# CH32F203CBT6-R1.net
KiCad netlist of a schematic drawn in Altium Designer
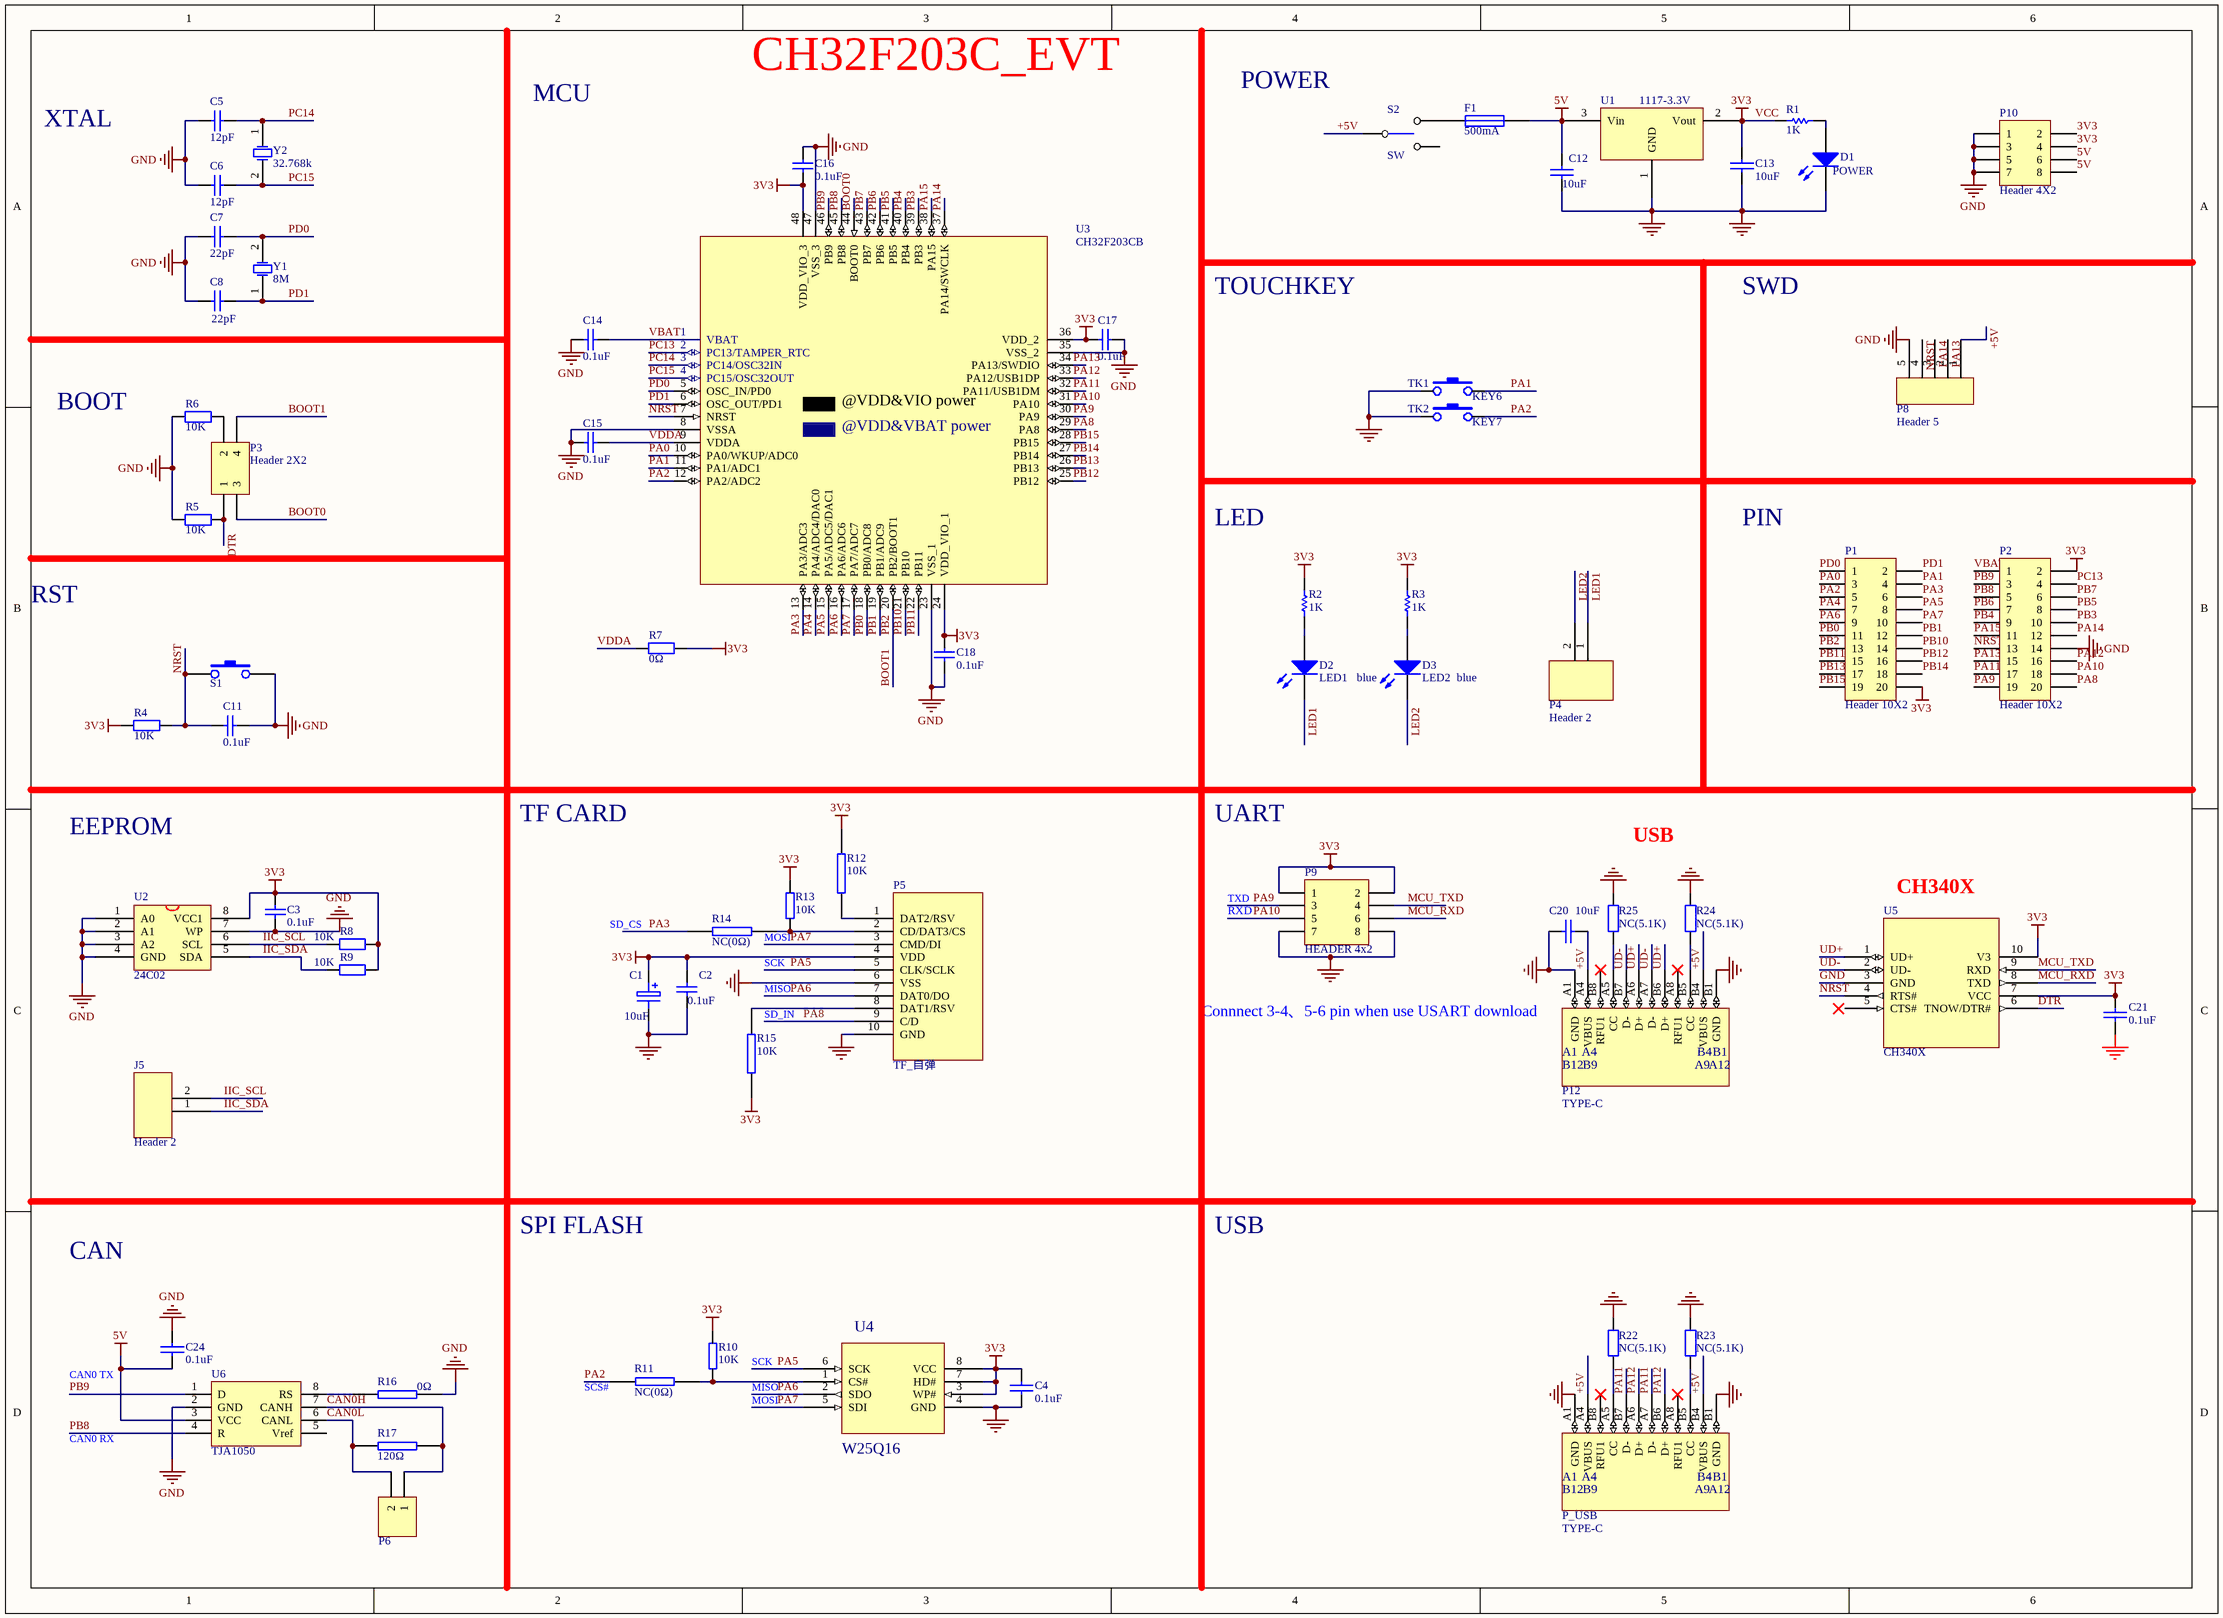
[diagram p0: CH32F203CBT6-R1.SchDoc]

(export (version "E")
  (design (tool "Eeschema 10.0.6"))
  (components
    (comp (ref "C1")
      (value "10uF")
      (footprint "3216")
      (description "Electrolytic Capacitor")
      (libsource (lib "*") (part "ELECTRO1"))
    )
    (comp (ref "C2")
      (value "0.1uF")
      (footprint "0603")
      (description "Capacitor")
      (fields (field (name "PUBLISHER") "Altium Limited"))
      (libsource (lib "*") (part "Cap"))
    )
    (comp (ref "C3")
      (value "0.1uF")
      (footprint "0603")
      (description "Capacitor")
      (fields (field (name "PUBLISHER") "Altium Limited"))
      (libsource (lib "Miscellaneous Devices") (part "Cap"))
    )
    (comp (ref "C4")
      (value "0.1uF")
      (footprint "0603")
      (description "Capacitor")
      (libsource (lib "*") (part "CAP"))
    )
    (comp (ref "C5")
      (value "12pF")
      (footprint "0603")
      (description "Capacitor")
      (fields (field (name "PUBLISHER") "Altium Limited"))
      (libsource (lib "Miscellaneous Devices") (part "Cap"))
    )
    (comp (ref "C6")
      (value "12pF")
      (footprint "0603")
      (description "Capacitor")
      (fields (field (name "PUBLISHER") "Altium Limited"))
      (libsource (lib "Miscellaneous Devices") (part "Cap"))
    )
    (comp (ref "C7")
      (value "22pF")
      (footprint "0603")
      (description "Capacitor")
      (fields (field (name "PUBLISHER") "Altium Limited"))
      (libsource (lib "Miscellaneous Devices") (part "Cap"))
    )
    (comp (ref "C8")
      (value "22pF")
      (footprint "0603")
      (description "Capacitor")
      (fields (field (name "PUBLISHER") "Altium Limited"))
      (libsource (lib "Miscellaneous Devices") (part "Cap"))
    )
    (comp (ref "C11")
      (value "0.1uF")
      (footprint "0603")
      (description "Capacitor")
      (fields (field (name "PUBLISHER") "Altium Limited"))
      (libsource (lib "Miscellaneous Devices") (part "Cap"))
    )
    (comp (ref "C12")
      (value "10uF")
      (footprint "3216")
      (description "Capacitor")
      (libsource (lib "") (part "CAP_1"))
    )
    (comp (ref "C13")
      (value "10uF")
      (footprint "0603")
      (description "Capacitor")
      (libsource (lib "") (part "CAP_1"))
    )
    (comp (ref "C14")
      (value "0.1uF")
      (footprint "0603")
      (description "Capacitor")
      (fields (field (name "PUBLISHER") "Altium Limited"))
      (libsource (lib "Miscellaneous Devices") (part "Cap"))
    )
    (comp (ref "C15")
      (value "0.1uF")
      (footprint "0603")
      (description "Capacitor")
      (fields (field (name "PUBLISHER") "Altium Limited"))
      (libsource (lib "Miscellaneous Devices") (part "Cap"))
    )
    (comp (ref "C16")
      (value "0.1uF")
      (footprint "0603")
      (description "Capacitor")
      (fields (field (name "PUBLISHER") "Altium Limited"))
      (libsource (lib "Miscellaneous Devices") (part "Cap"))
    )
    (comp (ref "C17")
      (value "0.1uF")
      (footprint "0603")
      (description "Capacitor")
      (fields (field (name "PUBLISHER") "Altium Limited"))
      (libsource (lib "Miscellaneous Devices") (part "Cap"))
    )
    (comp (ref "C18")
      (value "0.1uF")
      (footprint "0603")
      (description "Capacitor")
      (fields (field (name "PUBLISHER") "Altium Limited"))
      (libsource (lib "Miscellaneous Devices") (part "Cap"))
    )
    (comp (ref "C20")
      (value "10uF")
      (footprint "3216_C")
      (description "Capacitor")
      (libsource (lib "") (part "CAP_1"))
    )
    (comp (ref "C21")
      (value "0.1uF")
      (footprint "0603_C")
      (description "Capacitor")
      (libsource (lib "") (part "CAP_1"))
    )
    (comp (ref "C24")
      (value "0.1uF")
      (footprint "0603")
      (description "Capacitor")
      (libsource (lib "*") (part "CAP"))
    )
    (comp (ref "D1")
      (value "POWER")
      (footprint "0603L")
      (description "Typical INFRARED GaAs LED")
      (fields (field (name "PUBLISHER") "Altium Limited"))
      (libsource (lib "Miscellaneous Devices") (part "LED0"))
    )
    (comp (ref "D2")
      (value "LED1   blue")
      (footprint "0603L")
      (description "Typical INFRARED GaAs LED")
      (fields (field (name "PUBLISHER") "Altium Limited"))
      (libsource (lib "Miscellaneous Devices") (part "LED0"))
    )
    (comp (ref "D3")
      (value "LED2  blue")
      (footprint "0603L")
      (description "Typical INFRARED GaAs LED")
      (fields (field (name "PUBLISHER") "Altium Limited"))
      (libsource (lib "Miscellaneous Devices") (part "LED0"))
    )
    (comp (ref "F1")
      (value "500mA")
      (footprint "0603")
      (description "Fuse")
      (libsource (lib "*") (part "FUSE1"))
    )
    (comp (ref "J5") (value "Header 2") (footprint "SIP2 - 40mil") (libsource (lib "") (part "2HEAD_1")))
    (comp (ref "P1")
      (value "Header 10X2")
      (footprint "IDC20")
      (description "Header, 10-Pin, Dual row")
      (fields (field (name "PUBLISHER") "Altium Limited"))
      (libsource (lib "Miscellaneous Connectors") (part "Header 10X2"))
    )
    (comp (ref "P2")
      (value "Header 10X2")
      (footprint "IDC20")
      (description "Header, 10-Pin, Dual row")
      (fields (field (name "PUBLISHER") "Altium Limited"))
      (libsource (lib "Miscellaneous Connectors") (part "Header 10X2"))
    )
    (comp (ref "P3")
      (value "Header 2X2")
      (footprint "HDR2X2")
      (description "Header, 2-Pin, Dual row")
      (fields (field (name "PUBLISHER") "Altium Limited"))
      (libsource (lib "Miscellaneous Connectors") (part "Header 2X2"))
    )
    (comp (ref "P4") (value "Header 2") (footprint "SIP2 - 40mil") (libsource (lib "MYSCH") (part "2HEAD")))
    (comp (ref "P5") (value "TF_自弹") (footprint "TF_CARD") (libsource (lib "*") (part "TF_自弹")))
    (comp (ref "P6")
      (value "Header 2")
      (footprint "PORT2 4.5MM")
      (description "Header, 2-Pin")
      (fields (field (name "PUBLISHER") "Altium Limited"))
      (libsource (lib "Miscellaneous Connectors") (part "Header 2"))
    )
    (comp (ref "P8")
      (value "Header 5")
      (footprint "SIP5 - 40mil")
      (libsource (lib "PCB_Project1") (part "2HEAD"))
    )
    (comp (ref "P9")
      (value "HEADER 4x2")
      (footprint "MYPCB:IDC8-2.54mm")
      (description "Header, 4-Pin, Dual row")
      (libsource (lib "wch_sch_others") (part "HEADER 4x2"))
    )
    (comp (ref "P10")
      (value "Header 4X2")
      (footprint "IDC8")
      (description "Header, 4-Pin, Dual row")
      (fields (field (name "PUBLISHER") "Altium Limited"))
      (libsource (lib "Miscellaneous Connectors") (part "Header 4X2"))
    )
    (comp (ref "P12")
      (value "TYPE-C")
      (footprint "TYPE-C-Receptacle-2.0")
      (libsource (lib "*") (part "TYPE-C1"))
    )
    (comp (ref "P_USB")
      (value "TYPE-C")
      (footprint "TYPE-C-Receptacle-2.0")
      (libsource (lib "*") (part "TYPE-C1"))
    )
    (comp (ref "R1")
      (value "1K")
      (footprint "0603")
      (description "Semiconductor Resistor")
      (fields (field (name "PUBLISHER") "Altium Limited"))
      (libsource (lib "Miscellaneous Devices") (part "Res Semi"))
    )
    (comp (ref "R2")
      (value "1K")
      (footprint "0603")
      (description "Semiconductor Resistor")
      (fields (field (name "PUBLISHER") "Altium Limited"))
      (libsource (lib "Miscellaneous Devices") (part "Res Semi"))
    )
    (comp (ref "R3")
      (value "1K")
      (footprint "0603")
      (description "Semiconductor Resistor")
      (fields (field (name "PUBLISHER") "Altium Limited"))
      (libsource (lib "Miscellaneous Devices") (part "Res Semi"))
    )
    (comp (ref "R4")
      (value "10K")
      (footprint "0603")
      (description "Resistor")
      (fields (field (name "PUBLISHER") "Altium Limited"))
      (libsource (lib "Miscellaneous Devices") (part "Res2"))
    )
    (comp (ref "R5")
      (value "10K")
      (footprint "0603")
      (description "Resistor")
      (fields (field (name "PUBLISHER") "Altium Limited"))
      (libsource (lib "Miscellaneous Devices") (part "Res2"))
    )
    (comp (ref "R6")
      (value "10K")
      (footprint "0603")
      (description "Resistor")
      (fields (field (name "PUBLISHER") "Altium Limited"))
      (libsource (lib "Miscellaneous Devices") (part "Res2"))
    )
    (comp (ref "R7")
      (value "0Ω")
      (footprint "0603")
      (description "Resistor")
      (fields (field (name "PUBLISHER") "Altium Limited"))
      (libsource (lib "Miscellaneous Devices") (part "Res2"))
    )
    (comp (ref "R8")
      (value "10K")
      (footprint "0603")
      (description "Resistor")
      (fields (field (name "PUBLISHER") "Altium Limited"))
      (libsource (lib "Miscellaneous Devices") (part "Res2"))
    )
    (comp (ref "R9")
      (value "10K")
      (footprint "0603")
      (description "Resistor")
      (fields (field (name "PUBLISHER") "Altium Limited"))
      (libsource (lib "Miscellaneous Devices") (part "Res2"))
    )
    (comp (ref "R10") (value "10K") (footprint "0603") (libsource (lib "*") (part "DZ")))
    (comp (ref "R11") (value "NC(0Ω)") (footprint "0603") (libsource (lib "*") (part "RES2")))
    (comp (ref "R12") (value "10K") (footprint "0603") (libsource (lib "*") (part "RES2")))
    (comp (ref "R13") (value "10K") (footprint "0603") (libsource (lib "*") (part "DZ")))
    (comp (ref "R14") (value "NC(0Ω)") (footprint "0603") (libsource (lib "*") (part "RES2")))
    (comp (ref "R15") (value "10K") (footprint "0603") (libsource (lib "*") (part "RES2")))
    (comp (ref "R16") (value "0Ω") (footprint "0603") (libsource (lib "*") (part "RES2")))
    (comp (ref "R17") (value "120Ω") (footprint "0603") (libsource (lib "*") (part "RES2")))
    (comp (ref "R22")
      (value "NC(5.1K)")
      (footprint "0603")
      (description "Resistor")
      (libsource (lib "") (part "Res2_1"))
    )
    (comp (ref "R23")
      (value "NC(5.1K)")
      (footprint "0603")
      (description "Resistor")
      (libsource (lib "") (part "Res2_1"))
    )
    (comp (ref "R24")
      (value "NC(5.1K)")
      (footprint "0603")
      (description "Resistor")
      (libsource (lib "") (part "Res2_1"))
    )
    (comp (ref "R25")
      (value "NC(5.1K)")
      (footprint "0603")
      (description "Resistor")
      (libsource (lib "") (part "Res2_1"))
    )
    (comp (ref "S1") (value "KEY") (footprint "贴片按键") (libsource (lib "CCDXPLIB") (part "KEY")))
    (comp (ref "S2") (value "SW") (footprint "KEY2") (libsource (lib "MYSCH") (part "SW")))
    (comp (ref "TK1") (value "KEY6") (footprint "KEY68") (libsource (lib "*") (part "KEY")))
    (comp (ref "TK2") (value "KEY7") (footprint "KEY68") (libsource (lib "*") (part "KEY")))
    (comp (ref "U1")
      (value "1117-3.3V")
      (footprint "SOT-223")
      (libsource (lib "wch_sch_others") (part "1117-3.3V"))
    )
    (comp (ref "U2") (value "24C02") (footprint "SOP8") (libsource (lib "Elite_SCH") (part "24C256")))
    (comp (ref "U3")
      (value "CH32F203CB")
      (footprint "LQFP48")
      (description "ARM M3 HD-MCU, 144MHz, 8*UART, 10*Timer, 4*OPA")
      (libsource (lib "CHXXX") (part "CH32F203CB"))
    )
    (comp (ref "U4")
      (value "W25Q16")
      (footprint "016 SO-8")
      (libsource (lib "*") (part "Pro89C.tmp_25F512_2"))
    )
    (comp (ref "U5")
      (value "CH340X")
      (footprint "MSOP10")
      (description "USB to TTL Serial / UART")
      (libsource (lib "CHXXX") (part "CH340X"))
    )
    (comp (ref "U6") (value "TJA1050") (footprint "SOP8") (libsource (lib "CAN") (part "Component_1")))
    (comp (ref "Y1")
      (value "8M")
      (footprint "XT62/28")
      (description "Crystal Oscillator")
      (fields (field (name "PUBLISHER") "Altium Limited"))
      (libsource (lib "Miscellaneous Devices") (part "XTAL"))
    )
    (comp (ref "Y2")
      (value "32.768k")
      (footprint "FC-135")
      (description "Crystal Oscillator")
      (fields (field (name "PUBLISHER") "Altium Limited"))
      (libsource (lib "Miscellaneous Devices") (part "XTAL"))
    )
  )
  (nets
    (net (code "1") (name "/+5V") (class "Default")
      (node (ref "C20") (pin "2") (pinfunction "2_2") (pintype "passive"))
      (node (ref "P12") (pin "A4") (pinfunction "VBUS_A4") (pintype "bidirectional"))
      (node (ref "P12") (pin "B4") (pinfunction "VBUS_B4") (pintype "bidirectional"))
      (node (ref "P8") (pin "1") (pintype "passive"))
      (node (ref "P_USB") (pin "A4") (pinfunction "VBUS_A4") (pintype "bidirectional"))
      (node (ref "P_USB") (pin "B4") (pinfunction "VBUS_B4") (pintype "bidirectional"))
      (node (ref "S2") (pin "1") (pinfunction "1_1") (pintype "passive"))
    )
    (net (code "3") (name "/BOOT0") (class "Default")
      (node (ref "P3") (pin "3") (pinfunction "3_3") (pintype "passive"))
      (node (ref "U3") (pin "44") (pinfunction "BOOT0_44") (pintype "input"))
    )
    (net (code "4") (name "/BOOT1") (class "Default")
      (node (ref "P1") (pin "13") (pinfunction "13_13") (pintype "passive"))
      (node (ref "P3") (pin "4") (pinfunction "4_4") (pintype "passive"))
      (node (ref "U3") (pin "20") (pinfunction "PB2/BOOT1_20") (pintype "bidirectional"))
    )
    (net (code "5") (name "/CAN0H") (class "Default")
      (node (ref "P6") (pin "1") (pinfunction "1_1") (pintype "passive"))
      (node (ref "R17") (pin "1") (pinfunction "1_1") (pintype "passive"))
      (node (ref "U6") (pin "7") (pinfunction "CANH_7") (pintype "passive"))
    )
    (net (code "6") (name "/CAN0L") (class "Default")
      (node (ref "P6") (pin "2") (pinfunction "2_2") (pintype "passive"))
      (node (ref "R17") (pin "2") (pinfunction "2_2") (pintype "passive"))
      (node (ref "U6") (pin "6") (pinfunction "CANL_6") (pintype "passive"))
    )
    (net (code "7") (name "/DTR") (class "Default")
      (node (ref "P3") (pin "1") (pinfunction "1_1") (pintype "passive"))
      (node (ref "R5") (pin "1") (pinfunction "1_1") (pintype "passive"))
      (node (ref "U5") (pin "6") (pinfunction "TNOW/DTR#_6") (pintype "output"))
    )
    (net (code "8") (name "/IIC_SCL") (class "Default")
      (node (ref "J5") (pin "2") (pintype "passive"))
      (node (ref "R8") (pin "2") (pinfunction "2_2") (pintype "passive"))
      (node (ref "U2") (pin "6") (pinfunction "SCL_6") (pintype "passive"))
    )
    (net (code "9") (name "/IIC_SDA") (class "Default")
      (node (ref "J5") (pin "1") (pintype "passive"))
      (node (ref "R9") (pin "2") (pinfunction "2_2") (pintype "passive"))
      (node (ref "U2") (pin "5") (pinfunction "SDA_5") (pintype "passive"))
    )
    (net (code "10") (name "/LED1") (class "Default")
      (node (ref "D2") (pin "2") (pinfunction "K_2") (pintype "passive"))
      (node (ref "P4") (pin "1") (pintype "passive"))
    )
    (net (code "11") (name "/LED2") (class "Default")
      (node (ref "D3") (pin "2") (pinfunction "K_2") (pintype "passive"))
      (node (ref "P4") (pin "2") (pintype "passive"))
    )
    (net (code "12") (name "/MCU_RXD") (class "Default")
      (node (ref "P9") (pin "6") (pinfunction "6_6") (pintype "passive"))
      (node (ref "U5") (pin "8") (pinfunction "TXD_8") (pintype "output"))
    )
    (net (code "13") (name "/MCU_TXD") (class "Default")
      (node (ref "P9") (pin "4") (pinfunction "4_4") (pintype "passive"))
      (node (ref "U5") (pin "9") (pinfunction "RXD_9") (pintype "input"))
    )
    (net (code "14") (name "/NRST") (class "Default")
      (node (ref "C11") (pin "2") (pinfunction "2_2") (pintype "passive"))
      (node (ref "P2") (pin "13") (pinfunction "13_13") (pintype "passive"))
      (node (ref "P8") (pin "4") (pintype "passive"))
      (node (ref "R4") (pin "1") (pinfunction "1_1") (pintype "passive"))
      (node (ref "S1") (pin "1") (pinfunction "1_1") (pintype "passive"))
      (node (ref "U3") (pin "7") (pinfunction "NRST_7") (pintype "input"))
      (node (ref "U5") (pin "4") (pinfunction "RTS#_4") (pintype "output"))
    )
    (net (code "15") (name "/PA0") (class "Default")
      (node (ref "P1") (pin "3") (pinfunction "3_3") (pintype "passive"))
      (node (ref "U3") (pin "10") (pinfunction "PA0/WKUP/ADC0_10") (pintype "bidirectional"))
    )
    (net (code "16") (name "/PA1") (class "Default")
      (node (ref "P1") (pin "4") (pinfunction "4_4") (pintype "passive"))
      (node (ref "TK1") (pin "1") (pintype "passive"))
      (node (ref "U3") (pin "11") (pinfunction "PA1/ADC1_11") (pintype "bidirectional"))
    )
    (net (code "17") (name "/PA2") (class "Default")
      (node (ref "P1") (pin "5") (pinfunction "5_5") (pintype "passive"))
      (node (ref "R11") (pin "2") (pinfunction "2_2") (pintype "passive"))
      (node (ref "TK2") (pin "1") (pintype "passive"))
      (node (ref "U3") (pin "12") (pinfunction "PA2/ADC2_12") (pintype "bidirectional"))
    )
    (net (code "18") (name "/PA3") (class "Default")
      (node (ref "P1") (pin "6") (pinfunction "6_6") (pintype "passive"))
      (node (ref "R14") (pin "2") (pinfunction "2_2") (pintype "passive"))
      (node (ref "U3") (pin "13") (pinfunction "PA3/ADC3_13") (pintype "bidirectional"))
    )
    (net (code "19") (name "/PA4") (class "Default")
      (node (ref "P1") (pin "7") (pinfunction "7_7") (pintype "passive"))
      (node (ref "U3") (pin "14") (pinfunction "PA4/ADC4/DAC0_14") (pintype "bidirectional"))
    )
    (net (code "20") (name "/PA5") (class "Default")
      (node (ref "P1") (pin "8") (pinfunction "8_8") (pintype "passive"))
      (node (ref "P5") (pin "5") (pinfunction "CLK/SCLK_5") (pintype "passive"))
      (node (ref "U3") (pin "15") (pinfunction "PA5/ADC5/DAC1_15") (pintype "bidirectional"))
      (node (ref "U4") (pin "6") (pinfunction "SCK_6") (pintype "input"))
    )
    (net (code "21") (name "/PA6") (class "Default")
      (node (ref "P1") (pin "9") (pinfunction "9_9") (pintype "passive"))
      (node (ref "P5") (pin "7") (pinfunction "DAT0/DO_7") (pintype "passive"))
      (node (ref "U3") (pin "16") (pinfunction "PA6/ADC6_16") (pintype "bidirectional"))
      (node (ref "U4") (pin "2") (pinfunction "SDO_2") (pintype "output"))
    )
    (net (code "22") (name "/PA7") (class "Default")
      (node (ref "P1") (pin "10") (pinfunction "10_10") (pintype "passive"))
      (node (ref "P5") (pin "3") (pinfunction "CMD/DI_3") (pintype "passive"))
      (node (ref "U3") (pin "17") (pinfunction "PA7/ADC7_17") (pintype "bidirectional"))
      (node (ref "U4") (pin "5") (pinfunction "SDI_5") (pintype "input"))
    )
    (net (code "23") (name "/PA8") (class "Default")
      (node (ref "P2") (pin "20") (pinfunction "20_20") (pintype "passive"))
      (node (ref "P5") (pin "9") (pinfunction "C/D_9") (pintype "passive"))
      (node (ref "U3") (pin "29") (pinfunction "PA8_29") (pintype "bidirectional"))
    )
    (net (code "24") (name "/PA9") (class "Default")
      (node (ref "P2") (pin "19") (pinfunction "19_19") (pintype "passive"))
      (node (ref "P9") (pin "3") (pinfunction "3_3") (pintype "passive"))
      (node (ref "U3") (pin "30") (pinfunction "PA9_30") (pintype "bidirectional"))
    )
    (net (code "25") (name "/PA10") (class "Default")
      (node (ref "P2") (pin "18") (pinfunction "18_18") (pintype "passive"))
      (node (ref "P9") (pin "5") (pinfunction "5_5") (pintype "passive"))
      (node (ref "U3") (pin "31") (pinfunction "PA10_31") (pintype "bidirectional"))
    )
    (net (code "26") (name "/PA11") (class "Default")
      (node (ref "P2") (pin "17") (pinfunction "17_17") (pintype "passive"))
      (node (ref "P_USB") (pin "A7") (pinfunction "D-_A7") (pintype "bidirectional"))
      (node (ref "P_USB") (pin "B7") (pinfunction "D-_B7") (pintype "bidirectional"))
      (node (ref "U3") (pin "32") (pinfunction "PA11/USB1DM_32") (pintype "bidirectional"))
    )
    (net (code "27") (name "/PA12") (class "Default")
      (node (ref "P2") (pin "16") (pinfunction "16_16") (pintype "passive"))
      (node (ref "P_USB") (pin "A6") (pinfunction "D+_A6") (pintype "bidirectional"))
      (node (ref "P_USB") (pin "B6") (pinfunction "D+_B6") (pintype "bidirectional"))
      (node (ref "U3") (pin "33") (pinfunction "PA12/USB1DP_33") (pintype "bidirectional"))
    )
    (net (code "28") (name "/PA13") (class "Default")
      (node (ref "P2") (pin "15") (pinfunction "15_15") (pintype "passive"))
      (node (ref "P8") (pin "2") (pintype "passive"))
      (node (ref "U3") (pin "34") (pinfunction "PA13/SWDIO_34") (pintype "bidirectional"))
    )
    (net (code "29") (name "/PA14") (class "Default")
      (node (ref "P2") (pin "12") (pinfunction "12_12") (pintype "passive"))
      (node (ref "P8") (pin "3") (pintype "passive"))
      (node (ref "U3") (pin "37") (pinfunction "PA14/SWCLK_37") (pintype "bidirectional"))
    )
    (net (code "30") (name "/PA15") (class "Default")
      (node (ref "P2") (pin "11") (pinfunction "11_11") (pintype "passive"))
      (node (ref "U3") (pin "38") (pinfunction "PA15_38") (pintype "bidirectional"))
    )
    (net (code "31") (name "/PB0") (class "Default")
      (node (ref "P1") (pin "11") (pinfunction "11_11") (pintype "passive"))
      (node (ref "U3") (pin "18") (pinfunction "PB0/ADC8_18") (pintype "bidirectional"))
    )
    (net (code "32") (name "/PB1") (class "Default")
      (node (ref "P1") (pin "12") (pinfunction "12_12") (pintype "passive"))
      (node (ref "U3") (pin "19") (pinfunction "PB1/ADC9_19") (pintype "bidirectional"))
    )
    (net (code "33") (name "/PB3") (class "Default")
      (node (ref "P2") (pin "10") (pinfunction "10_10") (pintype "passive"))
      (node (ref "U3") (pin "39") (pinfunction "PB3_39") (pintype "bidirectional"))
    )
    (net (code "34") (name "/PB4") (class "Default")
      (node (ref "P2") (pin "9") (pinfunction "9_9") (pintype "passive"))
      (node (ref "U3") (pin "40") (pinfunction "PB4_40") (pintype "bidirectional"))
    )
    (net (code "35") (name "/PB5") (class "Default")
      (node (ref "P2") (pin "8") (pinfunction "8_8") (pintype "passive"))
      (node (ref "U3") (pin "41") (pinfunction "PB5_41") (pintype "bidirectional"))
    )
    (net (code "36") (name "/PB6") (class "Default")
      (node (ref "P2") (pin "7") (pinfunction "7_7") (pintype "passive"))
      (node (ref "U3") (pin "42") (pinfunction "PB6_42") (pintype "bidirectional"))
    )
    (net (code "37") (name "/PB7") (class "Default")
      (node (ref "P2") (pin "6") (pinfunction "6_6") (pintype "passive"))
      (node (ref "U3") (pin "43") (pinfunction "PB7_43") (pintype "bidirectional"))
    )
    (net (code "38") (name "/PB8") (class "Default")
      (node (ref "P2") (pin "5") (pinfunction "5_5") (pintype "passive"))
      (node (ref "U3") (pin "45") (pinfunction "PB8_45") (pintype "bidirectional"))
      (node (ref "U6") (pin "4") (pinfunction "R_4") (pintype "passive"))
    )
    (net (code "39") (name "/PB9") (class "Default")
      (node (ref "P2") (pin "3") (pinfunction "3_3") (pintype "passive"))
      (node (ref "U3") (pin "46") (pinfunction "PB9_46") (pintype "bidirectional"))
      (node (ref "U6") (pin "1") (pinfunction "D_1") (pintype "passive"))
    )
    (net (code "40") (name "/PB10") (class "Default")
      (node (ref "P1") (pin "14") (pinfunction "14_14") (pintype "passive"))
      (node (ref "U3") (pin "21") (pinfunction "PB10_21") (pintype "bidirectional"))
    )
    (net (code "41") (name "/PB11") (class "Default")
      (node (ref "P1") (pin "15") (pinfunction "15_15") (pintype "passive"))
      (node (ref "U3") (pin "22") (pinfunction "PB11_22") (pintype "bidirectional"))
    )
    (net (code "42") (name "/PB12") (class "Default")
      (node (ref "P1") (pin "16") (pinfunction "16_16") (pintype "passive"))
      (node (ref "U3") (pin "25") (pinfunction "PB12_25") (pintype "bidirectional"))
    )
    (net (code "43") (name "/PB13") (class "Default")
      (node (ref "P1") (pin "17") (pinfunction "17_17") (pintype "passive"))
      (node (ref "U3") (pin "26") (pinfunction "PB13_26") (pintype "bidirectional"))
    )
    (net (code "44") (name "/PB14") (class "Default")
      (node (ref "P1") (pin "18") (pinfunction "18_18") (pintype "passive"))
      (node (ref "U3") (pin "27") (pinfunction "PB14_27") (pintype "bidirectional"))
    )
    (net (code "45") (name "/PB15") (class "Default")
      (node (ref "P1") (pin "19") (pinfunction "19_19") (pintype "passive"))
      (node (ref "U3") (pin "28") (pinfunction "PB15_28") (pintype "bidirectional"))
    )
    (net (code "46") (name "/PC13") (class "Default")
      (node (ref "P2") (pin "4") (pinfunction "4_4") (pintype "passive"))
      (node (ref "U3") (pin "2") (pinfunction "PC13/TAMPER_RTC_2") (pintype "bidirectional"))
    )
    (net (code "47") (name "/PC14") (class "Default")
      (node (ref "C5") (pin "1") (pinfunction "1_1") (pintype "passive"))
      (node (ref "U3") (pin "3") (pinfunction "PC14/OSC32IN_3") (pintype "bidirectional"))
      (node (ref "Y2") (pin "1") (pinfunction "OSC1_1") (pintype "passive"))
    )
    (net (code "48") (name "/PC15") (class "Default")
      (node (ref "C6") (pin "1") (pinfunction "1_1") (pintype "passive"))
      (node (ref "U3") (pin "4") (pinfunction "PC15/OSC32OUT_4") (pintype "bidirectional"))
      (node (ref "Y2") (pin "2") (pinfunction "OSC2_2") (pintype "passive"))
    )
    (net (code "49") (name "/PD0") (class "Default")
      (node (ref "C7") (pin "2") (pinfunction "2_2") (pintype "passive"))
      (node (ref "P1") (pin "1") (pinfunction "1_1") (pintype "passive"))
      (node (ref "U3") (pin "5") (pinfunction "OSC_IN/PD0_5") (pintype "bidirectional"))
      (node (ref "Y1") (pin "2") (pinfunction "OSC2_2") (pintype "passive"))
    )
    (net (code "50") (name "/PD1") (class "Default")
      (node (ref "C8") (pin "2") (pinfunction "2_2") (pintype "passive"))
      (node (ref "P1") (pin "2") (pinfunction "2_2") (pintype "passive"))
      (node (ref "U3") (pin "6") (pinfunction "OSC_OUT/PD1_6") (pintype "bidirectional"))
      (node (ref "Y1") (pin "1") (pinfunction "OSC1_1") (pintype "passive"))
    )
    (net (code "51") (name "/UD+") (class "Default")
      (node (ref "P12") (pin "A6") (pinfunction "D+_A6") (pintype "bidirectional"))
      (node (ref "P12") (pin "B6") (pinfunction "D+_B6") (pintype "bidirectional"))
      (node (ref "U5") (pin "1") (pinfunction "UD+_1") (pintype "bidirectional"))
    )
    (net (code "52") (name "/UD-") (class "Default")
      (node (ref "P12") (pin "A7") (pinfunction "D-_A7") (pintype "bidirectional"))
      (node (ref "P12") (pin "B7") (pinfunction "D-_B7") (pintype "bidirectional"))
      (node (ref "U5") (pin "2") (pinfunction "UD-_2") (pintype "bidirectional"))
    )
    (net (code "53") (name "/VBAT") (class "Default")
      (node (ref "C14") (pin "1") (pinfunction "1_1") (pintype "passive"))
      (node (ref "P2") (pin "1") (pinfunction "1_1") (pintype "passive"))
      (node (ref "U3") (pin "1") (pinfunction "VBAT_1") (pintype "power_in"))
    )
    (net (code "54") (name "/VDDA") (class "Default")
      (node (ref "C15") (pin "1") (pinfunction "1_1") (pintype "passive"))
      (node (ref "R7") (pin "2") (pinfunction "2_2") (pintype "passive"))
      (node (ref "U3") (pin "9") (pinfunction "VDDA_9") (pintype "power_in"))
    )
    (net (code "55") (name "3V3") (class "Default")
      (node (ref "C1") (pin "1") (pinfunction "1_1") (pintype "passive"))
      (node (ref "C13") (pin "1") (pinfunction "1_1") (pintype "passive"))
      (node (ref "C16") (pin "2") (pinfunction "2_2") (pintype "passive"))
      (node (ref "C17") (pin "2") (pinfunction "2_2") (pintype "passive"))
      (node (ref "C18") (pin "2") (pinfunction "2_2") (pintype "passive"))
      (node (ref "C2") (pin "1") (pinfunction "1_1") (pintype "passive"))
      (node (ref "C21") (pin "1") (pinfunction "1_1") (pintype "passive"))
      (node (ref "C3") (pin "2") (pinfunction "2_2") (pintype "passive"))
      (node (ref "C4") (pin "2") (pinfunction "2_2") (pintype "passive"))
      (node (ref "P1") (pin "20") (pinfunction "20_20") (pintype "passive"))
      (node (ref "P10") (pin "2") (pinfunction "2_2") (pintype "passive"))
      (node (ref "P10") (pin "4") (pinfunction "4_4") (pintype "passive"))
      (node (ref "P2") (pin "2") (pinfunction "2_2") (pintype "passive"))
      (node (ref "P5") (pin "4") (pinfunction "VDD_4") (pintype "passive"))
      (node (ref "P9") (pin "1") (pinfunction "1_1") (pintype "passive"))
      (node (ref "P9") (pin "2") (pinfunction "2_2") (pintype "passive"))
      (node (ref "R1") (pin "2") (pinfunction "2_2") (pintype "passive"))
      (node (ref "R10") (pin "2") (pintype "passive"))
      (node (ref "R12") (pin "2") (pinfunction "2_2") (pintype "passive"))
      (node (ref "R13") (pin "2") (pintype "passive"))
      (node (ref "R15") (pin "1") (pinfunction "1_1") (pintype "passive"))
      (node (ref "R2") (pin "1") (pinfunction "1_1") (pintype "passive"))
      (node (ref "R3") (pin "1") (pinfunction "1_1") (pintype "passive"))
      (node (ref "R4") (pin "2") (pinfunction "2_2") (pintype "passive"))
      (node (ref "R7") (pin "1") (pinfunction "1_1") (pintype "passive"))
      (node (ref "R8") (pin "1") (pinfunction "1_1") (pintype "passive"))
      (node (ref "R9") (pin "1") (pinfunction "1_1") (pintype "passive"))
      (node (ref "U1") (pin "2") (pinfunction "Vout_2") (pintype "passive"))
      (node (ref "U2") (pin "8") (pinfunction "VCC1_8") (pintype "passive"))
      (node (ref "U3") (pin "24") (pinfunction "VDD_VIO_1_24") (pintype "power_in"))
      (node (ref "U3") (pin "36") (pinfunction "VDD_2_36") (pintype "power_in"))
      (node (ref "U3") (pin "48") (pinfunction "VDD_VIO_3_48") (pintype "power_in"))
      (node (ref "U4") (pin "3") (pinfunction "WP#_3") (pintype "input"))
      (node (ref "U4") (pin "7") (pinfunction "HD#_7") (pintype "power_in"))
      (node (ref "U4") (pin "8") (pinfunction "VCC_8") (pintype "power_in"))
      (node (ref "U5") (pin "10") (pinfunction "V3_10") (pintype "power_in"))
      (node (ref "U5") (pin "7") (pinfunction "VCC_7") (pintype "power_in"))
    )
    (net (code "56") (name "5V") (class "Default")
      (node (ref "C12") (pin "1") (pinfunction "1_1") (pintype "passive"))
      (node (ref "C24") (pin "2") (pinfunction "2_2") (pintype "passive"))
      (node (ref "F1") (pin "2") (pinfunction "2_2") (pintype "passive"))
      (node (ref "P10") (pin "6") (pinfunction "6_6") (pintype "passive"))
      (node (ref "P10") (pin "8") (pinfunction "8_8") (pintype "passive"))
      (node (ref "U1") (pin "3") (pinfunction "Vin_3") (pintype "passive"))
      (node (ref "U6") (pin "3") (pinfunction "VCC_3") (pintype "passive"))
    )
    (net (code "57") (name "GND") (class "Default")
      (node (ref "C1") (pin "2") (pinfunction "2_2") (pintype "passive"))
      (node (ref "C11") (pin "1") (pinfunction "1_1") (pintype "passive"))
      (node (ref "C12") (pin "2") (pinfunction "2_2") (pintype "passive"))
      (node (ref "C13") (pin "2") (pinfunction "2_2") (pintype "passive"))
      (node (ref "C14") (pin "2") (pinfunction "2_2") (pintype "passive"))
      (node (ref "C15") (pin "2") (pinfunction "2_2") (pintype "passive"))
      (node (ref "C16") (pin "1") (pinfunction "1_1") (pintype "passive"))
      (node (ref "C17") (pin "1") (pinfunction "1_1") (pintype "passive"))
      (node (ref "C18") (pin "1") (pinfunction "1_1") (pintype "passive"))
      (node (ref "C2") (pin "2") (pinfunction "2_2") (pintype "passive"))
      (node (ref "C20") (pin "1") (pinfunction "1_1") (pintype "passive"))
      (node (ref "C21") (pin "2") (pinfunction "2_2") (pintype "passive"))
      (node (ref "C24") (pin "1") (pinfunction "1_1") (pintype "passive"))
      (node (ref "C3") (pin "1") (pinfunction "1_1") (pintype "passive"))
      (node (ref "C4") (pin "1") (pinfunction "1_1") (pintype "passive"))
      (node (ref "C5") (pin "2") (pinfunction "2_2") (pintype "passive"))
      (node (ref "C6") (pin "2") (pinfunction "2_2") (pintype "passive"))
      (node (ref "C7") (pin "1") (pinfunction "1_1") (pintype "passive"))
      (node (ref "C8") (pin "1") (pinfunction "1_1") (pintype "passive"))
      (node (ref "D1") (pin "2") (pinfunction "K_2") (pintype "passive"))
      (node (ref "P10") (pin "1") (pinfunction "1_1") (pintype "passive"))
      (node (ref "P10") (pin "3") (pinfunction "3_3") (pintype "passive"))
      (node (ref "P10") (pin "5") (pinfunction "5_5") (pintype "passive"))
      (node (ref "P10") (pin "7") (pinfunction "7_7") (pintype "passive"))
      (node (ref "P12") (pin "A1") (pinfunction "GND_A1") (pintype "bidirectional"))
      (node (ref "P12") (pin "B1") (pinfunction "GND_B1") (pintype "bidirectional"))
      (node (ref "P2") (pin "14") (pinfunction "14_14") (pintype "passive"))
      (node (ref "P5") (pin "10") (pinfunction "GND_10") (pintype "passive"))
      (node (ref "P5") (pin "6") (pinfunction "VSS_6") (pintype "passive"))
      (node (ref "P8") (pin "5") (pintype "passive"))
      (node (ref "P9") (pin "7") (pinfunction "7_7") (pintype "passive"))
      (node (ref "P9") (pin "8") (pinfunction "8_8") (pintype "passive"))
      (node (ref "P_USB") (pin "A1") (pinfunction "GND_A1") (pintype "bidirectional"))
      (node (ref "P_USB") (pin "B1") (pinfunction "GND_B1") (pintype "bidirectional"))
      (node (ref "R16") (pin "1") (pinfunction "1_1") (pintype "passive"))
      (node (ref "R22") (pin "2") (pinfunction "2_2") (pintype "passive"))
      (node (ref "R23") (pin "2") (pinfunction "2_2") (pintype "passive"))
      (node (ref "R24") (pin "2") (pinfunction "2_2") (pintype "passive"))
      (node (ref "R25") (pin "2") (pinfunction "2_2") (pintype "passive"))
      (node (ref "R5") (pin "2") (pinfunction "2_2") (pintype "passive"))
      (node (ref "R6") (pin "2") (pinfunction "2_2") (pintype "passive"))
      (node (ref "S1") (pin "3") (pinfunction "3_3") (pintype "passive"))
      (node (ref "TK1") (pin "3") (pintype "passive"))
      (node (ref "TK2") (pin "3") (pintype "passive"))
      (node (ref "U1") (pin "1") (pinfunction "GND_1") (pintype "passive"))
      (node (ref "U2") (pin "1") (pinfunction "A0_1") (pintype "passive"))
      (node (ref "U2") (pin "2") (pinfunction "A1_2") (pintype "passive"))
      (node (ref "U2") (pin "3") (pinfunction "A2_3") (pintype "passive"))
      (node (ref "U2") (pin "4") (pinfunction "GND_4") (pintype "passive"))
      (node (ref "U2") (pin "7") (pinfunction "WP_7") (pintype "passive"))
      (node (ref "U3") (pin "23") (pinfunction "VSS_1_23") (pintype "power_in"))
      (node (ref "U3") (pin "35") (pinfunction "VSS_2_35") (pintype "power_in"))
      (node (ref "U3") (pin "47") (pinfunction "VSS_3_47") (pintype "power_in"))
      (node (ref "U3") (pin "8") (pinfunction "VSSA_8") (pintype "power_in"))
      (node (ref "U4") (pin "4") (pinfunction "GND_4") (pintype "power_in"))
      (node (ref "U5") (pin "3") (pinfunction "GND_3") (pintype "power_in"))
      (node (ref "U6") (pin "2") (pinfunction "GND_2") (pintype "passive"))
    )
    (net (code "58") (name "Net-(D1-A)") (class "Default")
      (node (ref "D1") (pin "1") (pinfunction "A_1") (pintype "passive"))
      (node (ref "R1") (pin "1") (pinfunction "1_1") (pintype "passive"))
    )
    (net (code "59") (name "Net-(D2-A)") (class "Default")
      (node (ref "D2") (pin "1") (pinfunction "A_1") (pintype "passive"))
      (node (ref "R2") (pin "2") (pinfunction "2_2") (pintype "passive"))
    )
    (net (code "60") (name "Net-(D3-A)") (class "Default")
      (node (ref "D3") (pin "1") (pinfunction "A_1") (pintype "passive"))
      (node (ref "R3") (pin "2") (pinfunction "2_2") (pintype "passive"))
    )
    (net (code "61") (name "Net-(F1-Pad1)") (class "Default")
      (node (ref "F1") (pin "1") (pinfunction "1_1") (pintype "passive"))
      (node (ref "S2") (pin "2") (pinfunction "2_2") (pintype "passive"))
    )
    (net (code "62") (name "Net-(P3-Pad2)") (class "Default")
      (node (ref "P3") (pin "2") (pinfunction "2_2") (pintype "passive"))
      (node (ref "R6") (pin "1") (pinfunction "1_1") (pintype "passive"))
    )
    (net (code "63") (name "Net-(P5-CD{slash}DAT3{slash}CS)") (class "Default")
      (node (ref "P5") (pin "2") (pinfunction "CD/DAT3/CS_2") (pintype "passive"))
      (node (ref "R13") (pin "1") (pintype "passive"))
      (node (ref "R14") (pin "1") (pinfunction "1_1") (pintype "passive"))
    )
    (net (code "64") (name "Net-(P5-DAT1{slash}RSV)") (class "Default")
      (node (ref "P5") (pin "8") (pinfunction "DAT1/RSV_8") (pintype "passive"))
      (node (ref "R15") (pin "2") (pinfunction "2_2") (pintype "passive"))
    )
    (net (code "65") (name "Net-(P5-DAT2{slash}RSV)") (class "Default")
      (node (ref "P5") (pin "1") (pinfunction "DAT2/RSV_1") (pintype "passive"))
      (node (ref "R12") (pin "1") (pinfunction "1_1") (pintype "passive"))
    )
    (net (code "66") (name "Net-(P12-CC-PadA5)") (class "Default")
      (node (ref "P12") (pin "A5") (pinfunction "CC_A5") (pintype "bidirectional"))
      (node (ref "R25") (pin "1") (pinfunction "1_1") (pintype "passive"))
    )
    (net (code "67") (name "Net-(P12-CC-PadB5)") (class "Default")
      (node (ref "P12") (pin "B5") (pinfunction "CC_B5") (pintype "bidirectional"))
      (node (ref "R24") (pin "1") (pinfunction "1_1") (pintype "passive"))
    )
    (net (code "68") (name "Net-(P_USB-CC-PadA5)") (class "Default")
      (node (ref "P_USB") (pin "A5") (pinfunction "CC_A5") (pintype "bidirectional"))
      (node (ref "R22") (pin "1") (pinfunction "1_1") (pintype "passive"))
    )
    (net (code "69") (name "Net-(P_USB-CC-PadB5)") (class "Default")
      (node (ref "P_USB") (pin "B5") (pinfunction "CC_B5") (pintype "bidirectional"))
      (node (ref "R23") (pin "1") (pinfunction "1_1") (pintype "passive"))
    )
    (net (code "70") (name "Net-(U4-CS#)") (class "Default")
      (node (ref "R10") (pin "1") (pintype "passive"))
      (node (ref "R11") (pin "1") (pinfunction "1_1") (pintype "passive"))
      (node (ref "U4") (pin "1") (pinfunction "CS#_1") (pintype "input"))
    )
    (net (code "71") (name "Net-(U6-RS)") (class "Default")
      (node (ref "R16") (pin "2") (pinfunction "2_2") (pintype "passive"))
      (node (ref "U6") (pin "8") (pinfunction "RS_8") (pintype "passive"))
    )
    (net (code "72") (name "unconnected-(P12-RFU1-PadA8)") (class "Default")
      (node (ref "P12") (pin "A8") (pinfunction "RFU1_A8") (pintype "bidirectional+no_connect"))
    )
    (net (code "73") (name "unconnected-(P12-RFU1-PadB8)") (class "Default")
      (node (ref "P12") (pin "B8") (pinfunction "RFU1_B8") (pintype "bidirectional+no_connect"))
    )
    (net (code "74") (name "unconnected-(P_USB-RFU1-PadA8)") (class "Default")
      (node (ref "P_USB") (pin "A8") (pinfunction "RFU1_A8") (pintype "bidirectional+no_connect"))
    )
    (net (code "75") (name "unconnected-(P_USB-RFU1-PadB8)") (class "Default")
      (node (ref "P_USB") (pin "B8") (pinfunction "RFU1_B8") (pintype "bidirectional+no_connect"))
    )
    (net (code "76") (name "unconnected-(S2-Pad3)") (class "Default")
      (node (ref "S2") (pin "3") (pinfunction "3_3") (pintype "passive"))
    )
    (net (code "77") (name "unconnected-(U5-CTS#-Pad5)") (class "Default")
      (node (ref "U5") (pin "5") (pinfunction "CTS#_5") (pintype "input"))
    )
    (net (code "78") (name "unconnected-(U6-Vref-Pad5)") (class "Default")
      (node (ref "U6") (pin "5") (pinfunction "Vref_5") (pintype "passive"))
    )
  )
)
